# Sensor.net
KiCad netlist of a schematic drawn in Altium Designer
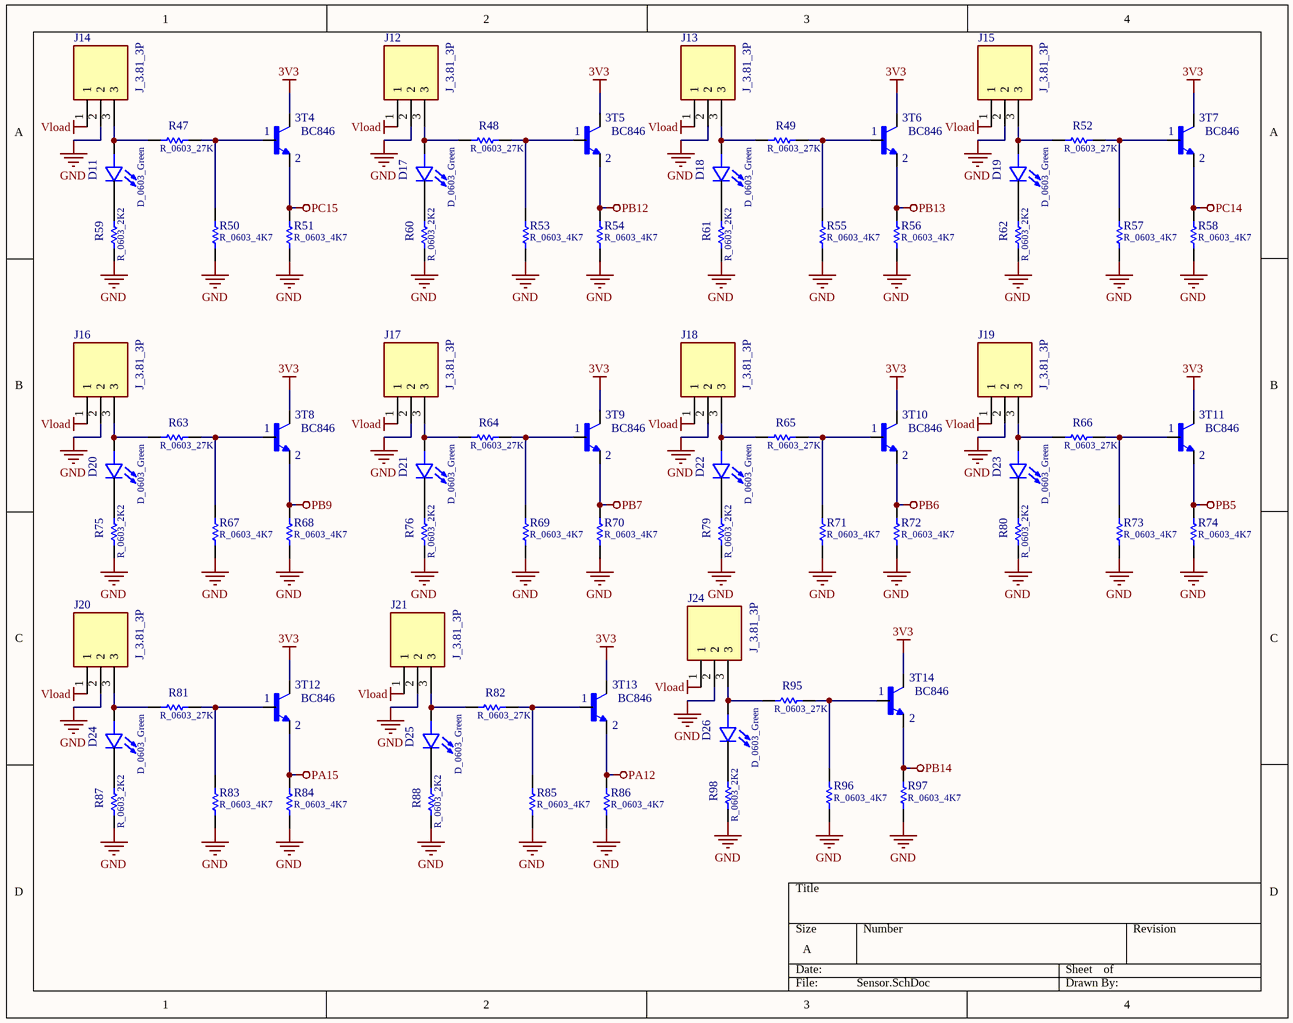
[diagram p0: Sensor.SchDoc]

(export (version "E")
  (design (tool "Eeschema 10.0.6"))
  (components
    (comp (ref "D11")
      (value "D_0603_Green")
      (footprint "Led 0603")
      (description "Led")
      (fields (field (name "MP") "SML-D12FWT86") (field (name "MF") "Rohm"))
      (libsource (lib "HUE") (part "Led"))
    )
    (comp (ref "D17")
      (value "D_0603_Green")
      (footprint "Led 0603")
      (description "Led")
      (fields (field (name "MP") "SML-D12FWT86") (field (name "MF") "Rohm"))
      (libsource (lib "HUE") (part "Led"))
    )
    (comp (ref "D18")
      (value "D_0603_Green")
      (footprint "Led 0603")
      (description "Led")
      (fields (field (name "MP") "SML-D12FWT86") (field (name "MF") "Rohm"))
      (libsource (lib "HUE") (part "Led"))
    )
    (comp (ref "D19")
      (value "D_0603_Green")
      (footprint "Led 0603")
      (description "Led")
      (fields (field (name "MP") "SML-D12FWT86") (field (name "MF") "Rohm"))
      (libsource (lib "HUE") (part "Led"))
    )
    (comp (ref "D20")
      (value "D_0603_Green")
      (footprint "Led 0603")
      (description "Led")
      (fields (field (name "MP") "SML-D12FWT86") (field (name "MF") "Rohm"))
      (libsource (lib "HUE") (part "Led"))
    )
    (comp (ref "D21")
      (value "D_0603_Green")
      (footprint "Led 0603")
      (description "Led")
      (fields (field (name "MP") "SML-D12FWT86") (field (name "MF") "Rohm"))
      (libsource (lib "HUE") (part "Led"))
    )
    (comp (ref "D22")
      (value "D_0603_Green")
      (footprint "Led 0603")
      (description "Led")
      (fields (field (name "MP") "SML-D12FWT86") (field (name "MF") "Rohm"))
      (libsource (lib "HUE") (part "Led"))
    )
    (comp (ref "D23")
      (value "D_0603_Green")
      (footprint "Led 0603")
      (description "Led")
      (fields (field (name "MP") "SML-D12FWT86") (field (name "MF") "Rohm"))
      (libsource (lib "HUE") (part "Led"))
    )
    (comp (ref "D24")
      (value "D_0603_Green")
      (footprint "Led 0603")
      (description "Led")
      (fields (field (name "MP") "SML-D12FWT86") (field (name "MF") "Rohm"))
      (libsource (lib "HUE") (part "Led"))
    )
    (comp (ref "D25")
      (value "D_0603_Green")
      (footprint "Led 0603")
      (description "Led")
      (fields (field (name "MP") "SML-D12FWT86") (field (name "MF") "Rohm"))
      (libsource (lib "HUE") (part "Led"))
    )
    (comp (ref "D26")
      (value "D_0603_Green")
      (footprint "Led 0603")
      (description "Led")
      (fields (field (name "MP") "SML-D12FWT86") (field (name "MF") "Rohm"))
      (libsource (lib "HUE") (part "Led"))
    )
    (comp (ref "J12")
      (value "J_3.81_3P")
      (footprint "3 Pin PCB TB 3.81")
      (fields (field (name "MF") "{'manufacturer': u'CUI'}") (field (name "MP") "TBP02R1-381-03BE"))
      (libsource (lib "HUE") (part "3 Pin PCB Terminal Block"))
    )
    (comp (ref "J13")
      (value "J_3.81_3P")
      (footprint "3 Pin PCB TB 3.81")
      (fields (field (name "MF") "{'manufacturer': u'CUI'}") (field (name "MP") "TBP02R1-381-03BE"))
      (libsource (lib "HUE") (part "3 Pin PCB Terminal Block"))
    )
    (comp (ref "J14")
      (value "J_3.81_3P")
      (footprint "3 Pin PCB TB 3.81")
      (fields (field (name "MF") "{'manufacturer': u'CUI'}") (field (name "MP") "TBP02R1-381-03BE"))
      (libsource (lib "HUE") (part "3 Pin PCB Terminal Block"))
    )
    (comp (ref "J15")
      (value "J_3.81_3P")
      (footprint "3 Pin PCB TB 3.81")
      (fields (field (name "MF") "{'manufacturer': u'CUI'}") (field (name "MP") "TBP02R1-381-03BE"))
      (libsource (lib "HUE") (part "3 Pin PCB Terminal Block"))
    )
    (comp (ref "J16")
      (value "J_3.81_3P")
      (footprint "3 Pin PCB TB 3.81")
      (fields (field (name "MF") "{'manufacturer': u'CUI'}") (field (name "MP") "TBP02R1-381-03BE"))
      (libsource (lib "HUE") (part "3 Pin PCB Terminal Block"))
    )
    (comp (ref "J17")
      (value "J_3.81_3P")
      (footprint "3 Pin PCB TB 3.81")
      (fields (field (name "MF") "{'manufacturer': u'CUI'}") (field (name "MP") "TBP02R1-381-03BE"))
      (libsource (lib "HUE") (part "3 Pin PCB Terminal Block"))
    )
    (comp (ref "J18")
      (value "J_3.81_3P")
      (footprint "3 Pin PCB TB 3.81")
      (fields (field (name "MF") "{'manufacturer': u'CUI'}") (field (name "MP") "TBP02R1-381-03BE"))
      (libsource (lib "HUE") (part "3 Pin PCB Terminal Block"))
    )
    (comp (ref "J19")
      (value "J_3.81_3P")
      (footprint "3 Pin PCB TB 3.81")
      (fields (field (name "MF") "{'manufacturer': u'CUI'}") (field (name "MP") "TBP02R1-381-03BE"))
      (libsource (lib "HUE") (part "3 Pin PCB Terminal Block"))
    )
    (comp (ref "J20")
      (value "J_3.81_3P")
      (footprint "3 Pin PCB TB 3.81")
      (fields (field (name "MF") "{'manufacturer': u'CUI'}") (field (name "MP") "TBP02R1-381-03BE"))
      (libsource (lib "HUE") (part "3 Pin PCB Terminal Block"))
    )
    (comp (ref "J21")
      (value "J_3.81_3P")
      (footprint "3 Pin PCB TB 3.81")
      (fields (field (name "MF") "{'manufacturer': u'CUI'}") (field (name "MP") "TBP02R1-381-03BE"))
      (libsource (lib "HUE") (part "3 Pin PCB Terminal Block"))
    )
    (comp (ref "J24")
      (value "J_3.81_3P")
      (footprint "3 Pin PCB TB 3.81")
      (fields (field (name "MF") "{'manufacturer': u'CUI'}") (field (name "MP") "TBP02R1-381-03BE"))
      (libsource (lib "HUE") (part "3 Pin PCB Terminal Block"))
    )
    (comp (ref "R47")
      (value "R_0603_27K")
      (footprint "RES 0603")
      (description "Resistor")
      (fields (field (name "PUBLISHER") "Altium Limited"))
      (libsource (lib "HUE") (part "Res"))
    )
    (comp (ref "R48")
      (value "R_0603_27K")
      (footprint "RES 0603")
      (description "Resistor")
      (fields (field (name "PUBLISHER") "Altium Limited"))
      (libsource (lib "HUE") (part "Res"))
    )
    (comp (ref "R49")
      (value "R_0603_27K")
      (footprint "RES 0603")
      (description "Resistor")
      (fields (field (name "PUBLISHER") "Altium Limited"))
      (libsource (lib "HUE") (part "Res"))
    )
    (comp (ref "R50")
      (value "R_0603_4K7")
      (footprint "RES 0603")
      (description "Resistor")
      (fields (field (name "PUBLISHER") "Altium Limited"))
      (libsource (lib "HUE") (part "Res"))
    )
    (comp (ref "R51")
      (value "R_0603_4K7")
      (footprint "RES 0603")
      (description "Resistor")
      (fields (field (name "PUBLISHER") "Altium Limited"))
      (libsource (lib "HUE") (part "Res"))
    )
    (comp (ref "R52")
      (value "R_0603_27K")
      (footprint "RES 0603")
      (description "Resistor")
      (fields (field (name "PUBLISHER") "Altium Limited"))
      (libsource (lib "HUE") (part "Res"))
    )
    (comp (ref "R53")
      (value "R_0603_4K7")
      (footprint "RES 0603")
      (description "Resistor")
      (fields (field (name "PUBLISHER") "Altium Limited"))
      (libsource (lib "HUE") (part "Res"))
    )
    (comp (ref "R54")
      (value "R_0603_4K7")
      (footprint "RES 0603")
      (description "Resistor")
      (fields (field (name "PUBLISHER") "Altium Limited"))
      (libsource (lib "HUE") (part "Res"))
    )
    (comp (ref "R55")
      (value "R_0603_4K7")
      (footprint "RES 0603")
      (description "Resistor")
      (fields (field (name "PUBLISHER") "Altium Limited"))
      (libsource (lib "HUE") (part "Res"))
    )
    (comp (ref "R56")
      (value "R_0603_4K7")
      (footprint "RES 0603")
      (description "Resistor")
      (fields (field (name "PUBLISHER") "Altium Limited"))
      (libsource (lib "HUE") (part "Res"))
    )
    (comp (ref "R57")
      (value "R_0603_4K7")
      (footprint "RES 0603")
      (description "Resistor")
      (fields (field (name "PUBLISHER") "Altium Limited"))
      (libsource (lib "HUE") (part "Res"))
    )
    (comp (ref "R58")
      (value "R_0603_4K7")
      (footprint "RES 0603")
      (description "Resistor")
      (fields (field (name "PUBLISHER") "Altium Limited"))
      (libsource (lib "HUE") (part "Res"))
    )
    (comp (ref "R59")
      (value "R_0603_2K2")
      (footprint "RES 0603")
      (description "Resistor")
      (fields (field (name "PUBLISHER") "Altium Limited"))
      (libsource (lib "HUE") (part "Res"))
    )
    (comp (ref "R60")
      (value "R_0603_2K2")
      (footprint "RES 0603")
      (description "Resistor")
      (fields (field (name "PUBLISHER") "Altium Limited"))
      (libsource (lib "HUE") (part "Res"))
    )
    (comp (ref "R61")
      (value "R_0603_2K2")
      (footprint "RES 0603")
      (description "Resistor")
      (fields (field (name "PUBLISHER") "Altium Limited"))
      (libsource (lib "HUE") (part "Res"))
    )
    (comp (ref "R62")
      (value "R_0603_2K2")
      (footprint "RES 0603")
      (description "Resistor")
      (fields (field (name "PUBLISHER") "Altium Limited"))
      (libsource (lib "HUE") (part "Res"))
    )
    (comp (ref "R63")
      (value "R_0603_27K")
      (footprint "RES 0603")
      (description "Resistor")
      (fields (field (name "PUBLISHER") "Altium Limited"))
      (libsource (lib "HUE") (part "Res"))
    )
    (comp (ref "R64")
      (value "R_0603_27K")
      (footprint "RES 0603")
      (description "Resistor")
      (fields (field (name "PUBLISHER") "Altium Limited"))
      (libsource (lib "HUE") (part "Res"))
    )
    (comp (ref "R65")
      (value "R_0603_27K")
      (footprint "RES 0603")
      (description "Resistor")
      (fields (field (name "PUBLISHER") "Altium Limited"))
      (libsource (lib "HUE") (part "Res"))
    )
    (comp (ref "R66")
      (value "R_0603_27K")
      (footprint "RES 0603")
      (description "Resistor")
      (fields (field (name "PUBLISHER") "Altium Limited"))
      (libsource (lib "HUE") (part "Res"))
    )
    (comp (ref "R67")
      (value "R_0603_4K7")
      (footprint "RES 0603")
      (description "Resistor")
      (fields (field (name "PUBLISHER") "Altium Limited"))
      (libsource (lib "HUE") (part "Res"))
    )
    (comp (ref "R68")
      (value "R_0603_4K7")
      (footprint "RES 0603")
      (description "Resistor")
      (fields (field (name "PUBLISHER") "Altium Limited"))
      (libsource (lib "HUE") (part "Res"))
    )
    (comp (ref "R69")
      (value "R_0603_4K7")
      (footprint "RES 0603")
      (description "Resistor")
      (fields (field (name "PUBLISHER") "Altium Limited"))
      (libsource (lib "HUE") (part "Res"))
    )
    (comp (ref "R70")
      (value "R_0603_4K7")
      (footprint "RES 0603")
      (description "Resistor")
      (fields (field (name "PUBLISHER") "Altium Limited"))
      (libsource (lib "HUE") (part "Res"))
    )
    (comp (ref "R71")
      (value "R_0603_4K7")
      (footprint "RES 0603")
      (description "Resistor")
      (fields (field (name "PUBLISHER") "Altium Limited"))
      (libsource (lib "HUE") (part "Res"))
    )
    (comp (ref "R72")
      (value "R_0603_4K7")
      (footprint "RES 0603")
      (description "Resistor")
      (fields (field (name "PUBLISHER") "Altium Limited"))
      (libsource (lib "HUE") (part "Res"))
    )
    (comp (ref "R73")
      (value "R_0603_4K7")
      (footprint "RES 0603")
      (description "Resistor")
      (fields (field (name "PUBLISHER") "Altium Limited"))
      (libsource (lib "HUE") (part "Res"))
    )
    (comp (ref "R74")
      (value "R_0603_4K7")
      (footprint "RES 0603")
      (description "Resistor")
      (fields (field (name "PUBLISHER") "Altium Limited"))
      (libsource (lib "HUE") (part "Res"))
    )
    (comp (ref "R75")
      (value "R_0603_2K2")
      (footprint "RES 0603")
      (description "Resistor")
      (fields (field (name "PUBLISHER") "Altium Limited"))
      (libsource (lib "HUE") (part "Res"))
    )
    (comp (ref "R76")
      (value "R_0603_2K2")
      (footprint "RES 0603")
      (description "Resistor")
      (fields (field (name "PUBLISHER") "Altium Limited"))
      (libsource (lib "HUE") (part "Res"))
    )
    (comp (ref "R79")
      (value "R_0603_2K2")
      (footprint "RES 0603")
      (description "Resistor")
      (fields (field (name "PUBLISHER") "Altium Limited"))
      (libsource (lib "HUE") (part "Res"))
    )
    (comp (ref "R80")
      (value "R_0603_2K2")
      (footprint "RES 0603")
      (description "Resistor")
      (fields (field (name "PUBLISHER") "Altium Limited"))
      (libsource (lib "HUE") (part "Res"))
    )
    (comp (ref "R81")
      (value "R_0603_27K")
      (footprint "RES 0603")
      (description "Resistor")
      (fields (field (name "PUBLISHER") "Altium Limited"))
      (libsource (lib "HUE") (part "Res"))
    )
    (comp (ref "R82")
      (value "R_0603_27K")
      (footprint "RES 0603")
      (description "Resistor")
      (fields (field (name "PUBLISHER") "Altium Limited"))
      (libsource (lib "HUE") (part "Res"))
    )
    (comp (ref "R83")
      (value "R_0603_4K7")
      (footprint "RES 0603")
      (description "Resistor")
      (fields (field (name "PUBLISHER") "Altium Limited"))
      (libsource (lib "HUE") (part "Res"))
    )
    (comp (ref "R84")
      (value "R_0603_4K7")
      (footprint "RES 0603")
      (description "Resistor")
      (fields (field (name "PUBLISHER") "Altium Limited"))
      (libsource (lib "HUE") (part "Res"))
    )
    (comp (ref "R85")
      (value "R_0603_4K7")
      (footprint "RES 0603")
      (description "Resistor")
      (fields (field (name "PUBLISHER") "Altium Limited"))
      (libsource (lib "HUE") (part "Res"))
    )
    (comp (ref "R86")
      (value "R_0603_4K7")
      (footprint "RES 0603")
      (description "Resistor")
      (fields (field (name "PUBLISHER") "Altium Limited"))
      (libsource (lib "HUE") (part "Res"))
    )
    (comp (ref "R87")
      (value "R_0603_2K2")
      (footprint "RES 0603")
      (description "Resistor")
      (fields (field (name "PUBLISHER") "Altium Limited"))
      (libsource (lib "HUE") (part "Res"))
    )
    (comp (ref "R88")
      (value "R_0603_2K2")
      (footprint "RES 0603")
      (description "Resistor")
      (fields (field (name "PUBLISHER") "Altium Limited"))
      (libsource (lib "HUE") (part "Res"))
    )
    (comp (ref "R95")
      (value "R_0603_27K")
      (footprint "RES 0603")
      (description "Resistor")
      (fields (field (name "PUBLISHER") "Altium Limited"))
      (libsource (lib "HUE") (part "Res"))
    )
    (comp (ref "R96")
      (value "R_0603_4K7")
      (footprint "RES 0603")
      (description "Resistor")
      (fields (field (name "PUBLISHER") "Altium Limited"))
      (libsource (lib "HUE") (part "Res"))
    )
    (comp (ref "R97")
      (value "R_0603_4K7")
      (footprint "RES 0603")
      (description "Resistor")
      (fields (field (name "PUBLISHER") "Altium Limited"))
      (libsource (lib "HUE") (part "Res"))
    )
    (comp (ref "R98")
      (value "R_0603_2K2")
      (footprint "RES 0603")
      (description "Resistor")
      (fields (field (name "PUBLISHER") "Altium Limited"))
      (libsource (lib "HUE") (part "Res"))
    )
    (comp (ref "T4")
      (value "BC846")
      (footprint "SOT23")
      (fields (field (name "MF") "ON Semiconductor"))
      (libsource (lib "HUE") (part "BC846"))
    )
    (comp (ref "T5")
      (value "BC846")
      (footprint "SOT23")
      (fields (field (name "MF") "ON Semiconductor"))
      (libsource (lib "HUE") (part "BC846"))
    )
    (comp (ref "T6")
      (value "BC846")
      (footprint "SOT23")
      (fields (field (name "MF") "ON Semiconductor"))
      (libsource (lib "HUE") (part "BC846"))
    )
    (comp (ref "T7")
      (value "BC846")
      (footprint "SOT23")
      (fields (field (name "MF") "ON Semiconductor"))
      (libsource (lib "HUE") (part "BC846"))
    )
    (comp (ref "T8")
      (value "BC846")
      (footprint "SOT23")
      (fields (field (name "MF") "ON Semiconductor"))
      (libsource (lib "HUE") (part "BC846"))
    )
    (comp (ref "T9")
      (value "BC846")
      (footprint "SOT23")
      (fields (field (name "MF") "ON Semiconductor"))
      (libsource (lib "HUE") (part "BC846"))
    )
    (comp (ref "T10")
      (value "BC846")
      (footprint "SOT23")
      (fields (field (name "MF") "ON Semiconductor"))
      (libsource (lib "HUE") (part "BC846"))
    )
    (comp (ref "T11")
      (value "BC846")
      (footprint "SOT23")
      (fields (field (name "MF") "ON Semiconductor"))
      (libsource (lib "HUE") (part "BC846"))
    )
    (comp (ref "T12")
      (value "BC846")
      (footprint "SOT23")
      (fields (field (name "MF") "ON Semiconductor"))
      (libsource (lib "HUE") (part "BC846"))
    )
    (comp (ref "T13")
      (value "BC846")
      (footprint "SOT23")
      (fields (field (name "MF") "ON Semiconductor"))
      (libsource (lib "HUE") (part "BC846"))
    )
    (comp (ref "T14")
      (value "BC846")
      (footprint "SOT23")
      (fields (field (name "MF") "ON Semiconductor"))
      (libsource (lib "HUE") (part "BC846"))
    )
  )
  (nets
    (net (code "1") (name "3V3") (class "Default")
      (node (ref "T10") (pin "3") (pinfunction "C_3") (pintype "passive"))
      (node (ref "T11") (pin "3") (pinfunction "C_3") (pintype "passive"))
      (node (ref "T12") (pin "3") (pinfunction "C_3") (pintype "passive"))
      (node (ref "T13") (pin "3") (pinfunction "C_3") (pintype "passive"))
      (node (ref "T14") (pin "3") (pinfunction "C_3") (pintype "passive"))
      (node (ref "T4") (pin "3") (pinfunction "C_3") (pintype "passive"))
      (node (ref "T5") (pin "3") (pinfunction "C_3") (pintype "passive"))
      (node (ref "T6") (pin "3") (pinfunction "C_3") (pintype "passive"))
      (node (ref "T7") (pin "3") (pinfunction "C_3") (pintype "passive"))
      (node (ref "T8") (pin "3") (pinfunction "C_3") (pintype "passive"))
      (node (ref "T9") (pin "3") (pinfunction "C_3") (pintype "passive"))
    )
    (net (code "2") (name "GND") (class "Default")
      (node (ref "J12") (pin "2") (pinfunction "2_2") (pintype "passive"))
      (node (ref "J13") (pin "2") (pinfunction "2_2") (pintype "passive"))
      (node (ref "J14") (pin "2") (pinfunction "2_2") (pintype "passive"))
      (node (ref "J15") (pin "2") (pinfunction "2_2") (pintype "passive"))
      (node (ref "J16") (pin "2") (pinfunction "2_2") (pintype "passive"))
      (node (ref "J17") (pin "2") (pinfunction "2_2") (pintype "passive"))
      (node (ref "J18") (pin "2") (pinfunction "2_2") (pintype "passive"))
      (node (ref "J19") (pin "2") (pinfunction "2_2") (pintype "passive"))
      (node (ref "J20") (pin "2") (pinfunction "2_2") (pintype "passive"))
      (node (ref "J21") (pin "2") (pinfunction "2_2") (pintype "passive"))
      (node (ref "J24") (pin "2") (pinfunction "2_2") (pintype "passive"))
      (node (ref "R50") (pin "1") (pinfunction "1_1") (pintype "passive"))
      (node (ref "R51") (pin "1") (pinfunction "1_1") (pintype "passive"))
      (node (ref "R53") (pin "1") (pinfunction "1_1") (pintype "passive"))
      (node (ref "R54") (pin "1") (pinfunction "1_1") (pintype "passive"))
      (node (ref "R55") (pin "1") (pinfunction "1_1") (pintype "passive"))
      (node (ref "R56") (pin "1") (pinfunction "1_1") (pintype "passive"))
      (node (ref "R57") (pin "1") (pinfunction "1_1") (pintype "passive"))
      (node (ref "R58") (pin "1") (pinfunction "1_1") (pintype "passive"))
      (node (ref "R59") (pin "1") (pinfunction "1_1") (pintype "passive"))
      (node (ref "R60") (pin "1") (pinfunction "1_1") (pintype "passive"))
      (node (ref "R61") (pin "1") (pinfunction "1_1") (pintype "passive"))
      (node (ref "R62") (pin "1") (pinfunction "1_1") (pintype "passive"))
      (node (ref "R67") (pin "1") (pinfunction "1_1") (pintype "passive"))
      (node (ref "R68") (pin "1") (pinfunction "1_1") (pintype "passive"))
      (node (ref "R69") (pin "1") (pinfunction "1_1") (pintype "passive"))
      (node (ref "R70") (pin "1") (pinfunction "1_1") (pintype "passive"))
      (node (ref "R71") (pin "1") (pinfunction "1_1") (pintype "passive"))
      (node (ref "R72") (pin "1") (pinfunction "1_1") (pintype "passive"))
      (node (ref "R73") (pin "1") (pinfunction "1_1") (pintype "passive"))
      (node (ref "R74") (pin "1") (pinfunction "1_1") (pintype "passive"))
      (node (ref "R75") (pin "1") (pinfunction "1_1") (pintype "passive"))
      (node (ref "R76") (pin "1") (pinfunction "1_1") (pintype "passive"))
      (node (ref "R79") (pin "1") (pinfunction "1_1") (pintype "passive"))
      (node (ref "R80") (pin "1") (pinfunction "1_1") (pintype "passive"))
      (node (ref "R83") (pin "1") (pinfunction "1_1") (pintype "passive"))
      (node (ref "R84") (pin "1") (pinfunction "1_1") (pintype "passive"))
      (node (ref "R85") (pin "1") (pinfunction "1_1") (pintype "passive"))
      (node (ref "R86") (pin "1") (pinfunction "1_1") (pintype "passive"))
      (node (ref "R87") (pin "1") (pinfunction "1_1") (pintype "passive"))
      (node (ref "R88") (pin "1") (pinfunction "1_1") (pintype "passive"))
      (node (ref "R96") (pin "1") (pinfunction "1_1") (pintype "passive"))
      (node (ref "R97") (pin "1") (pinfunction "1_1") (pintype "passive"))
      (node (ref "R98") (pin "1") (pinfunction "1_1") (pintype "passive"))
    )
    (net (code "3") (name "Net-(D11-A)") (class "Default")
      (node (ref "D11") (pin "1") (pinfunction "A_1") (pintype "passive"))
      (node (ref "J14") (pin "3") (pinfunction "3_3") (pintype "passive"))
      (node (ref "R47") (pin "2") (pinfunction "2_2") (pintype "passive"))
    )
    (net (code "4") (name "Net-(D11-C)") (class "Default")
      (node (ref "D11") (pin "2") (pinfunction "C_2") (pintype "passive"))
      (node (ref "R59") (pin "2") (pinfunction "2_2") (pintype "passive"))
    )
    (net (code "5") (name "Net-(D17-A)") (class "Default")
      (node (ref "D17") (pin "1") (pinfunction "A_1") (pintype "passive"))
      (node (ref "J12") (pin "3") (pinfunction "3_3") (pintype "passive"))
      (node (ref "R48") (pin "2") (pinfunction "2_2") (pintype "passive"))
    )
    (net (code "6") (name "Net-(D17-C)") (class "Default")
      (node (ref "D17") (pin "2") (pinfunction "C_2") (pintype "passive"))
      (node (ref "R60") (pin "2") (pinfunction "2_2") (pintype "passive"))
    )
    (net (code "7") (name "Net-(D18-A)") (class "Default")
      (node (ref "D18") (pin "1") (pinfunction "A_1") (pintype "passive"))
      (node (ref "J13") (pin "3") (pinfunction "3_3") (pintype "passive"))
      (node (ref "R49") (pin "2") (pinfunction "2_2") (pintype "passive"))
    )
    (net (code "8") (name "Net-(D18-C)") (class "Default")
      (node (ref "D18") (pin "2") (pinfunction "C_2") (pintype "passive"))
      (node (ref "R61") (pin "2") (pinfunction "2_2") (pintype "passive"))
    )
    (net (code "9") (name "Net-(D19-A)") (class "Default")
      (node (ref "D19") (pin "1") (pinfunction "A_1") (pintype "passive"))
      (node (ref "J15") (pin "3") (pinfunction "3_3") (pintype "passive"))
      (node (ref "R52") (pin "2") (pinfunction "2_2") (pintype "passive"))
    )
    (net (code "10") (name "Net-(D19-C)") (class "Default")
      (node (ref "D19") (pin "2") (pinfunction "C_2") (pintype "passive"))
      (node (ref "R62") (pin "2") (pinfunction "2_2") (pintype "passive"))
    )
    (net (code "11") (name "Net-(D20-A)") (class "Default")
      (node (ref "D20") (pin "1") (pinfunction "A_1") (pintype "passive"))
      (node (ref "J16") (pin "3") (pinfunction "3_3") (pintype "passive"))
      (node (ref "R63") (pin "2") (pinfunction "2_2") (pintype "passive"))
    )
    (net (code "12") (name "Net-(D20-C)") (class "Default")
      (node (ref "D20") (pin "2") (pinfunction "C_2") (pintype "passive"))
      (node (ref "R75") (pin "2") (pinfunction "2_2") (pintype "passive"))
    )
    (net (code "13") (name "Net-(D21-A)") (class "Default")
      (node (ref "D21") (pin "1") (pinfunction "A_1") (pintype "passive"))
      (node (ref "J17") (pin "3") (pinfunction "3_3") (pintype "passive"))
      (node (ref "R64") (pin "2") (pinfunction "2_2") (pintype "passive"))
    )
    (net (code "14") (name "Net-(D21-C)") (class "Default")
      (node (ref "D21") (pin "2") (pinfunction "C_2") (pintype "passive"))
      (node (ref "R76") (pin "2") (pinfunction "2_2") (pintype "passive"))
    )
    (net (code "15") (name "Net-(D22-A)") (class "Default")
      (node (ref "D22") (pin "1") (pinfunction "A_1") (pintype "passive"))
      (node (ref "J18") (pin "3") (pinfunction "3_3") (pintype "passive"))
      (node (ref "R65") (pin "2") (pinfunction "2_2") (pintype "passive"))
    )
    (net (code "16") (name "Net-(D22-C)") (class "Default")
      (node (ref "D22") (pin "2") (pinfunction "C_2") (pintype "passive"))
      (node (ref "R79") (pin "2") (pinfunction "2_2") (pintype "passive"))
    )
    (net (code "17") (name "Net-(D23-A)") (class "Default")
      (node (ref "D23") (pin "1") (pinfunction "A_1") (pintype "passive"))
      (node (ref "J19") (pin "3") (pinfunction "3_3") (pintype "passive"))
      (node (ref "R66") (pin "2") (pinfunction "2_2") (pintype "passive"))
    )
    (net (code "18") (name "Net-(D23-C)") (class "Default")
      (node (ref "D23") (pin "2") (pinfunction "C_2") (pintype "passive"))
      (node (ref "R80") (pin "2") (pinfunction "2_2") (pintype "passive"))
    )
    (net (code "19") (name "Net-(D24-A)") (class "Default")
      (node (ref "D24") (pin "1") (pinfunction "A_1") (pintype "passive"))
      (node (ref "J20") (pin "3") (pinfunction "3_3") (pintype "passive"))
      (node (ref "R81") (pin "2") (pinfunction "2_2") (pintype "passive"))
    )
    (net (code "20") (name "Net-(D24-C)") (class "Default")
      (node (ref "D24") (pin "2") (pinfunction "C_2") (pintype "passive"))
      (node (ref "R87") (pin "2") (pinfunction "2_2") (pintype "passive"))
    )
    (net (code "21") (name "Net-(D25-A)") (class "Default")
      (node (ref "D25") (pin "1") (pinfunction "A_1") (pintype "passive"))
      (node (ref "J21") (pin "3") (pinfunction "3_3") (pintype "passive"))
      (node (ref "R82") (pin "2") (pinfunction "2_2") (pintype "passive"))
    )
    (net (code "22") (name "Net-(D25-C)") (class "Default")
      (node (ref "D25") (pin "2") (pinfunction "C_2") (pintype "passive"))
      (node (ref "R88") (pin "2") (pinfunction "2_2") (pintype "passive"))
    )
    (net (code "23") (name "Net-(D26-A)") (class "Default")
      (node (ref "D26") (pin "1") (pinfunction "A_1") (pintype "passive"))
      (node (ref "J24") (pin "3") (pinfunction "3_3") (pintype "passive"))
      (node (ref "R95") (pin "2") (pinfunction "2_2") (pintype "passive"))
    )
    (net (code "24") (name "Net-(D26-C)") (class "Default")
      (node (ref "D26") (pin "2") (pinfunction "C_2") (pintype "passive"))
      (node (ref "R98") (pin "2") (pinfunction "2_2") (pintype "passive"))
    )
    (net (code "25") (name "Net-(T4-B)") (class "Default")
      (node (ref "R47") (pin "1") (pinfunction "1_1") (pintype "passive"))
      (node (ref "R50") (pin "2") (pinfunction "2_2") (pintype "passive"))
      (node (ref "T4") (pin "1") (pinfunction "B_1") (pintype "passive"))
    )
    (net (code "26") (name "Net-(T5-B)") (class "Default")
      (node (ref "R48") (pin "1") (pinfunction "1_1") (pintype "passive"))
      (node (ref "R53") (pin "2") (pinfunction "2_2") (pintype "passive"))
      (node (ref "T5") (pin "1") (pinfunction "B_1") (pintype "passive"))
    )
    (net (code "27") (name "Net-(T6-B)") (class "Default")
      (node (ref "R49") (pin "1") (pinfunction "1_1") (pintype "passive"))
      (node (ref "R55") (pin "2") (pinfunction "2_2") (pintype "passive"))
      (node (ref "T6") (pin "1") (pinfunction "B_1") (pintype "passive"))
    )
    (net (code "28") (name "Net-(T7-B)") (class "Default")
      (node (ref "R52") (pin "1") (pinfunction "1_1") (pintype "passive"))
      (node (ref "R57") (pin "2") (pinfunction "2_2") (pintype "passive"))
      (node (ref "T7") (pin "1") (pinfunction "B_1") (pintype "passive"))
    )
    (net (code "29") (name "Net-(T8-B)") (class "Default")
      (node (ref "R63") (pin "1") (pinfunction "1_1") (pintype "passive"))
      (node (ref "R67") (pin "2") (pinfunction "2_2") (pintype "passive"))
      (node (ref "T8") (pin "1") (pinfunction "B_1") (pintype "passive"))
    )
    (net (code "30") (name "Net-(T9-B)") (class "Default")
      (node (ref "R64") (pin "1") (pinfunction "1_1") (pintype "passive"))
      (node (ref "R69") (pin "2") (pinfunction "2_2") (pintype "passive"))
      (node (ref "T9") (pin "1") (pinfunction "B_1") (pintype "passive"))
    )
    (net (code "31") (name "Net-(T10-B)") (class "Default")
      (node (ref "R65") (pin "1") (pinfunction "1_1") (pintype "passive"))
      (node (ref "R71") (pin "2") (pinfunction "2_2") (pintype "passive"))
      (node (ref "T10") (pin "1") (pinfunction "B_1") (pintype "passive"))
    )
    (net (code "32") (name "Net-(T11-B)") (class "Default")
      (node (ref "R66") (pin "1") (pinfunction "1_1") (pintype "passive"))
      (node (ref "R73") (pin "2") (pinfunction "2_2") (pintype "passive"))
      (node (ref "T11") (pin "1") (pinfunction "B_1") (pintype "passive"))
    )
    (net (code "33") (name "Net-(T12-B)") (class "Default")
      (node (ref "R81") (pin "1") (pinfunction "1_1") (pintype "passive"))
      (node (ref "R83") (pin "2") (pinfunction "2_2") (pintype "passive"))
      (node (ref "T12") (pin "1") (pinfunction "B_1") (pintype "passive"))
    )
    (net (code "34") (name "Net-(T13-B)") (class "Default")
      (node (ref "R82") (pin "1") (pinfunction "1_1") (pintype "passive"))
      (node (ref "R85") (pin "2") (pinfunction "2_2") (pintype "passive"))
      (node (ref "T13") (pin "1") (pinfunction "B_1") (pintype "passive"))
    )
    (net (code "35") (name "Net-(T14-B)") (class "Default")
      (node (ref "R95") (pin "1") (pinfunction "1_1") (pintype "passive"))
      (node (ref "R96") (pin "2") (pinfunction "2_2") (pintype "passive"))
      (node (ref "T14") (pin "1") (pinfunction "B_1") (pintype "passive"))
    )
    (net (code "36") (name "PA12") (class "Default")
      (node (ref "R86") (pin "2") (pinfunction "2_2") (pintype "passive"))
      (node (ref "T13") (pin "2") (pinfunction "E_2") (pintype "passive"))
    )
    (net (code "37") (name "PA15") (class "Default")
      (node (ref "R84") (pin "2") (pinfunction "2_2") (pintype "passive"))
      (node (ref "T12") (pin "2") (pinfunction "E_2") (pintype "passive"))
    )
    (net (code "38") (name "PB5") (class "Default")
      (node (ref "R74") (pin "2") (pinfunction "2_2") (pintype "passive"))
      (node (ref "T11") (pin "2") (pinfunction "E_2") (pintype "passive"))
    )
    (net (code "39") (name "PB6") (class "Default")
      (node (ref "R72") (pin "2") (pinfunction "2_2") (pintype "passive"))
      (node (ref "T10") (pin "2") (pinfunction "E_2") (pintype "passive"))
    )
    (net (code "40") (name "PB7") (class "Default")
      (node (ref "R70") (pin "2") (pinfunction "2_2") (pintype "passive"))
      (node (ref "T9") (pin "2") (pinfunction "E_2") (pintype "passive"))
    )
    (net (code "41") (name "PB9") (class "Default")
      (node (ref "R68") (pin "2") (pinfunction "2_2") (pintype "passive"))
      (node (ref "T8") (pin "2") (pinfunction "E_2") (pintype "passive"))
    )
    (net (code "42") (name "PB12") (class "Default")
      (node (ref "R54") (pin "2") (pinfunction "2_2") (pintype "passive"))
      (node (ref "T5") (pin "2") (pinfunction "E_2") (pintype "passive"))
    )
    (net (code "43") (name "PB13") (class "Default")
      (node (ref "R56") (pin "2") (pinfunction "2_2") (pintype "passive"))
      (node (ref "T6") (pin "2") (pinfunction "E_2") (pintype "passive"))
    )
    (net (code "44") (name "PB14") (class "Default")
      (node (ref "R97") (pin "2") (pinfunction "2_2") (pintype "passive"))
      (node (ref "T14") (pin "2") (pinfunction "E_2") (pintype "passive"))
    )
    (net (code "45") (name "PC14") (class "Default")
      (node (ref "R58") (pin "2") (pinfunction "2_2") (pintype "passive"))
      (node (ref "T7") (pin "2") (pinfunction "E_2") (pintype "passive"))
    )
    (net (code "46") (name "PC15") (class "Default")
      (node (ref "R51") (pin "2") (pinfunction "2_2") (pintype "passive"))
      (node (ref "T4") (pin "2") (pinfunction "E_2") (pintype "passive"))
    )
    (net (code "47") (name "Vload") (class "Default")
      (node (ref "J12") (pin "1") (pinfunction "1_1") (pintype "passive"))
      (node (ref "J13") (pin "1") (pinfunction "1_1") (pintype "passive"))
      (node (ref "J14") (pin "1") (pinfunction "1_1") (pintype "passive"))
      (node (ref "J15") (pin "1") (pinfunction "1_1") (pintype "passive"))
      (node (ref "J16") (pin "1") (pinfunction "1_1") (pintype "passive"))
      (node (ref "J17") (pin "1") (pinfunction "1_1") (pintype "passive"))
      (node (ref "J18") (pin "1") (pinfunction "1_1") (pintype "passive"))
      (node (ref "J19") (pin "1") (pinfunction "1_1") (pintype "passive"))
      (node (ref "J20") (pin "1") (pinfunction "1_1") (pintype "passive"))
      (node (ref "J21") (pin "1") (pinfunction "1_1") (pintype "passive"))
      (node (ref "J24") (pin "1") (pinfunction "1_1") (pintype "passive"))
    )
  )
)
